# Sheet0-mcu.net
KiCad netlist of a schematic drawn in Altium Designer
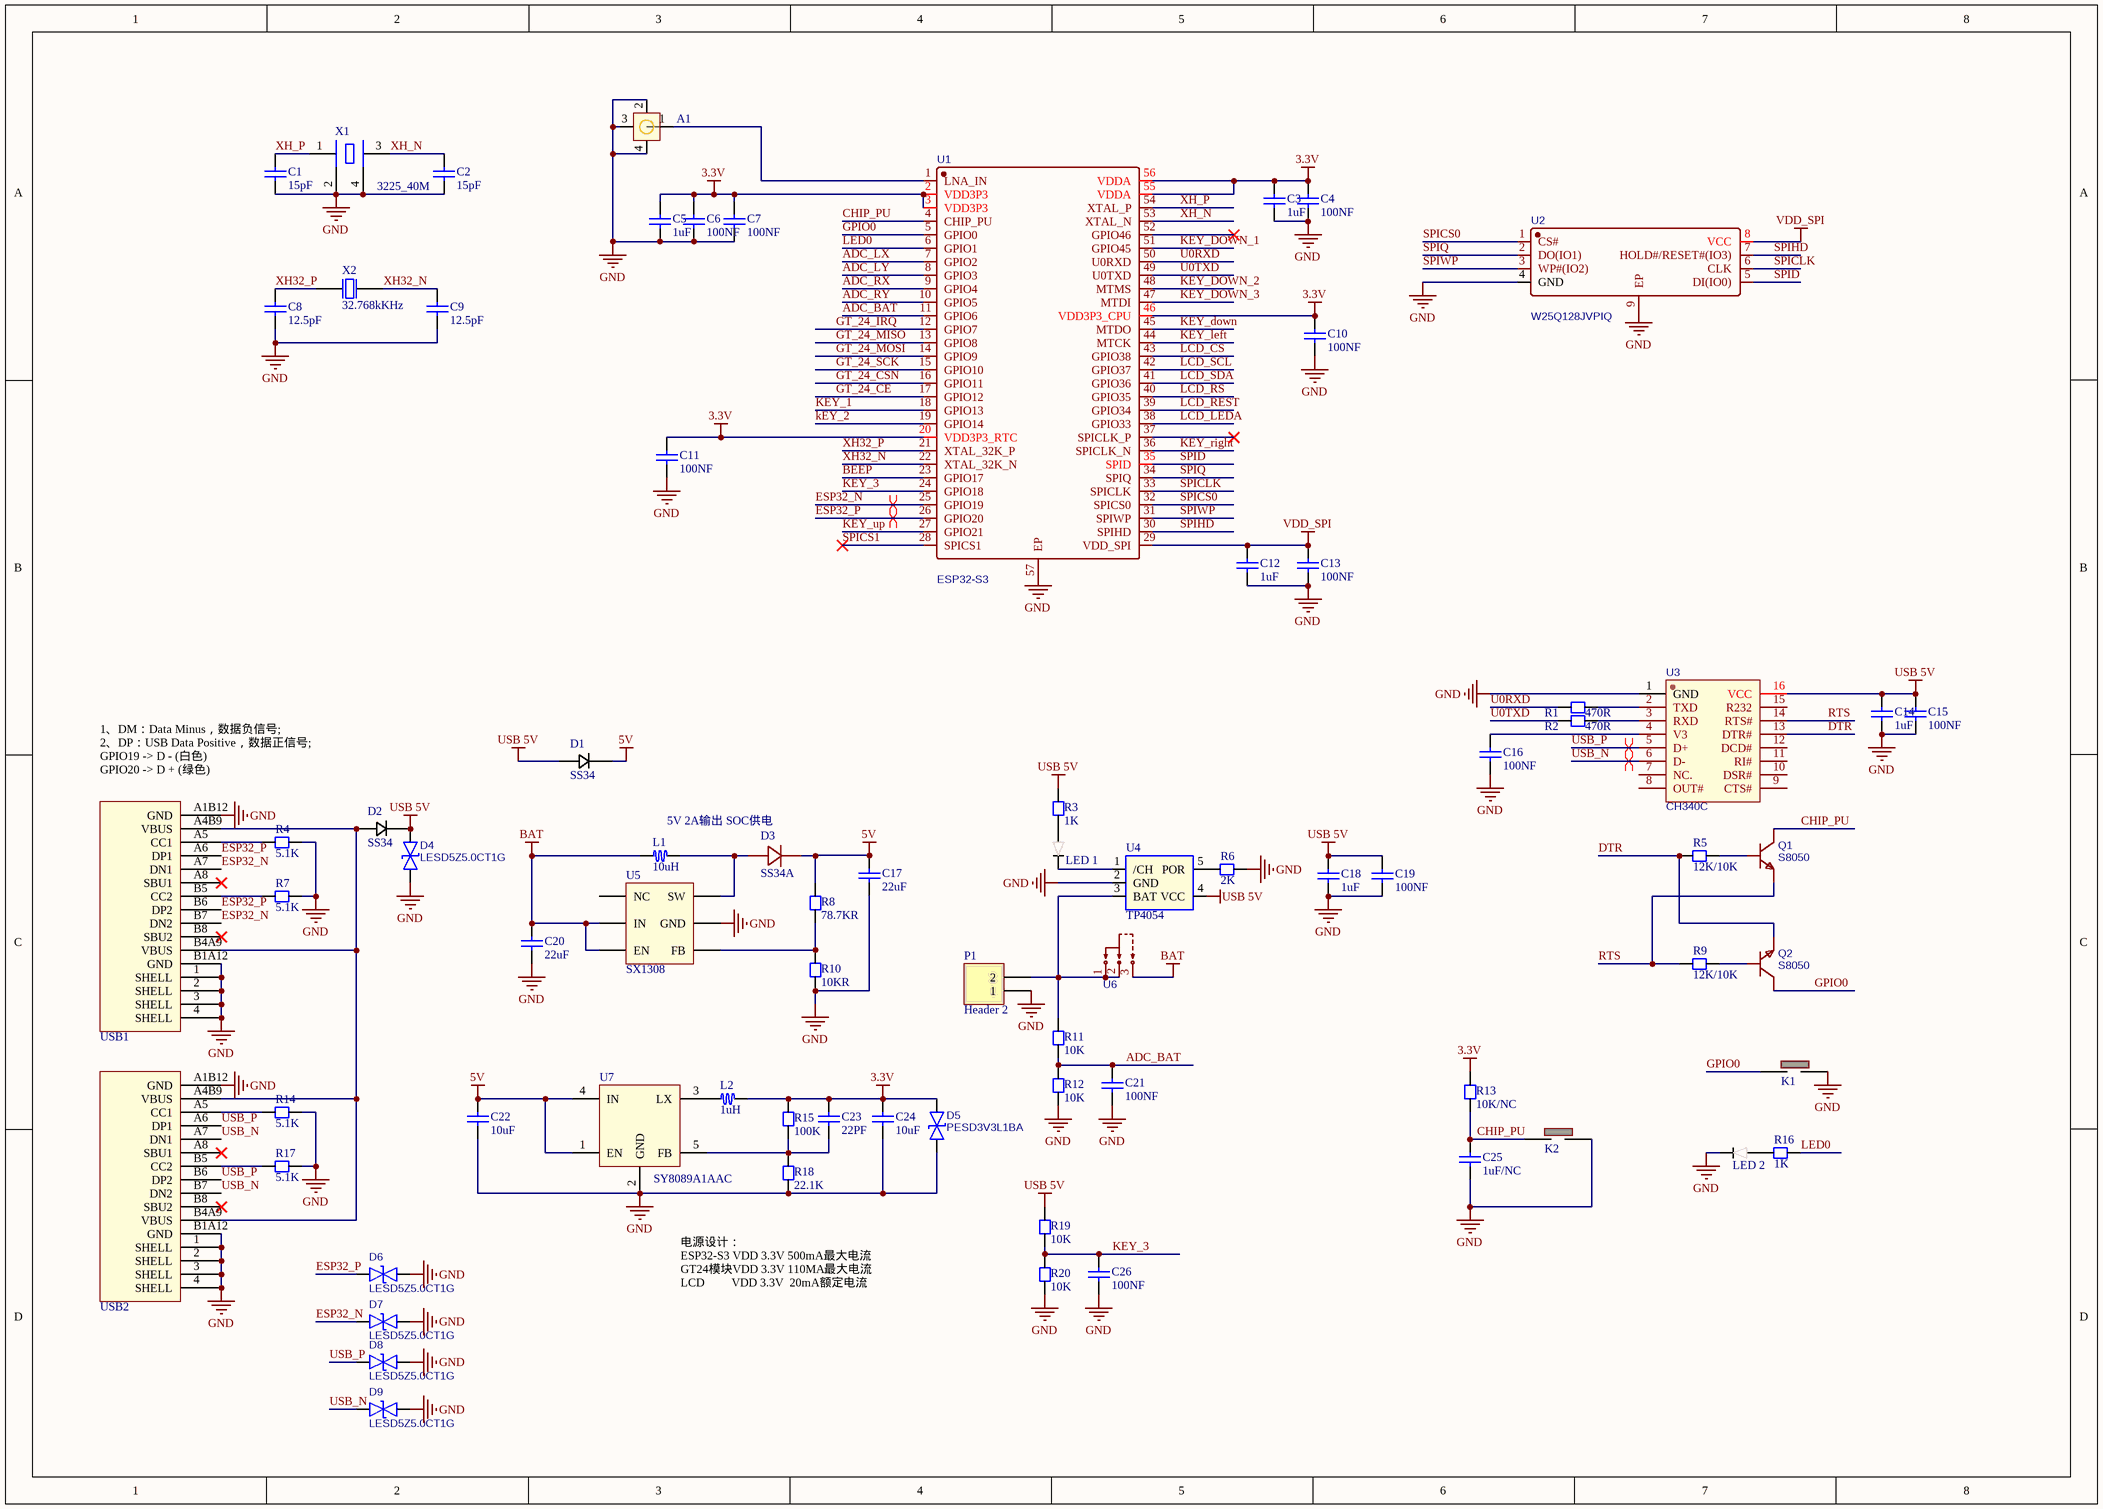
[diagram p0: Sheet0-mcu.SchDoc]

(export (version "E")
  (design (tool "Eeschema 10.0.6"))
  (components
    (comp (ref "A1")
      (value "ANT-IPEX")
      (footprint "ANT-IPEX")
      (description "贴片封装的天线 封装类型为IPEX")
      (libsource (lib "antenna") (part "ANT-IPEX"))
    )
    (comp (ref "C1")
      (value "15pF")
      (footprint "CC1608-0603")
      (description "0603封装的电容")
      (fields (field (name "PUBLISHER") "Altium Limited"))
      (libsource (lib "base") (part "Cap Chip 0603"))
    )
    (comp (ref "C2")
      (value "15pF")
      (footprint "CC1608-0603")
      (description "0603封装的电容")
      (fields (field (name "PUBLISHER") "Altium Limited"))
      (libsource (lib "base") (part "Cap Chip 0603"))
    )
    (comp (ref "C3")
      (value "1uF")
      (footprint "CC1608-0603")
      (description "0603封装的电容")
      (fields (field (name "PUBLISHER") "Altium Limited"))
      (libsource (lib "base") (part "Cap Chip 0603"))
    )
    (comp (ref "C4")
      (value "100NF")
      (footprint "CC1608-0603")
      (description "0603封装的电容")
      (fields (field (name "PUBLISHER") "Altium Limited"))
      (libsource (lib "base") (part "Cap Chip 0603"))
    )
    (comp (ref "C5")
      (value "1uF")
      (footprint "CC1608-0603")
      (description "0603封装的电容")
      (fields (field (name "PUBLISHER") "Altium Limited"))
      (libsource (lib "base") (part "Cap Chip 0603"))
    )
    (comp (ref "C6")
      (value "100NF")
      (footprint "CC1608-0603")
      (description "0603封装的电容")
      (fields (field (name "PUBLISHER") "Altium Limited"))
      (libsource (lib "base") (part "Cap Chip 0603"))
    )
    (comp (ref "C7")
      (value "100NF")
      (footprint "CC1608-0603")
      (description "0603封装的电容")
      (fields (field (name "PUBLISHER") "Altium Limited"))
      (libsource (lib "base") (part "Cap Chip 0603"))
    )
    (comp (ref "C8")
      (value "12.5pF")
      (footprint "CC1608-0603")
      (description "0603封装的电容")
      (fields (field (name "PUBLISHER") "Altium Limited"))
      (libsource (lib "base") (part "Cap Chip 0603"))
    )
    (comp (ref "C9")
      (value "12.5pF")
      (footprint "CC1608-0603")
      (description "0603封装的电容")
      (fields (field (name "PUBLISHER") "Altium Limited"))
      (libsource (lib "base") (part "Cap Chip 0603"))
    )
    (comp (ref "C10")
      (value "100NF")
      (footprint "CC1608-0603")
      (description "0603封装的电容")
      (fields (field (name "PUBLISHER") "Altium Limited"))
      (libsource (lib "base") (part "Cap Chip 0603"))
    )
    (comp (ref "C11")
      (value "100NF")
      (footprint "CC1608-0603")
      (description "0603封装的电容")
      (fields (field (name "PUBLISHER") "Altium Limited"))
      (libsource (lib "base") (part "Cap Chip 0603"))
    )
    (comp (ref "C12")
      (value "1uF")
      (footprint "CC1608-0603")
      (description "0603封装的电容")
      (fields (field (name "PUBLISHER") "Altium Limited"))
      (libsource (lib "base") (part "Cap Chip 0603"))
    )
    (comp (ref "C13")
      (value "100NF")
      (footprint "CC1608-0603")
      (description "0603封装的电容")
      (fields (field (name "PUBLISHER") "Altium Limited"))
      (libsource (lib "base") (part "Cap Chip 0603"))
    )
    (comp (ref "C14")
      (value "1uF")
      (footprint "CC1608-0603")
      (description "0603封装的电容")
      (fields (field (name "PUBLISHER") "Altium Limited"))
      (libsource (lib "base") (part "Cap Chip 0603"))
    )
    (comp (ref "C15")
      (value "100NF")
      (footprint "CC1608-0603")
      (description "0603封装的电容")
      (fields (field (name "PUBLISHER") "Altium Limited"))
      (libsource (lib "base") (part "Cap Chip 0603"))
    )
    (comp (ref "C16")
      (value "100NF")
      (footprint "CC1608-0603")
      (description "0603封装的电容")
      (fields (field (name "PUBLISHER") "Altium Limited"))
      (libsource (lib "base") (part "Cap Chip 0603"))
    )
    (comp (ref "C17")
      (value "22uF")
      (footprint "CC1608-0603")
      (description "贴片电容")
      (libsource (lib "tianxiaohua_Schlib") (part "Chip capacitor"))
    )
    (comp (ref "C18")
      (value "1uF")
      (footprint "CC1608-0603")
      (description "0603封装的电容")
      (fields (field (name "PUBLISHER") "Altium Limited"))
      (libsource (lib "base") (part "Cap Chip 0603"))
    )
    (comp (ref "C19")
      (value "100NF")
      (footprint "CC1608-0603")
      (description "0603封装的电容")
      (fields (field (name "PUBLISHER") "Altium Limited"))
      (libsource (lib "base") (part "Cap Chip 0603"))
    )
    (comp (ref "C20")
      (value "22uF")
      (footprint "CC1608-0603")
      (description "0603封装的电容")
      (fields (field (name "PUBLISHER") "Altium Limited"))
      (libsource (lib "base") (part "Cap Chip 0603"))
    )
    (comp (ref "C21")
      (value "100NF")
      (footprint "CC1608-0603")
      (description "0603封装的电容")
      (fields (field (name "PUBLISHER") "Altium Limited"))
      (libsource (lib "base") (part "Cap Chip 0603"))
    )
    (comp (ref "C22")
      (value "10uF")
      (footprint "CC1608-0603")
      (description "0603封装的电容")
      (fields (field (name "PUBLISHER") "Altium Limited"))
      (libsource (lib "base") (part "Cap Chip 0603"))
    )
    (comp (ref "C23")
      (value "22PF")
      (footprint "CC1608-0603")
      (description "0603封装的电容")
      (fields (field (name "PUBLISHER") "Altium Limited"))
      (libsource (lib "base") (part "Cap Chip 0603"))
    )
    (comp (ref "C24")
      (value "10uF")
      (footprint "CC1608-0603")
      (description "0603封装的电容")
      (fields (field (name "PUBLISHER") "Altium Limited"))
      (libsource (lib "base") (part "Cap Chip 0603"))
    )
    (comp (ref "C25")
      (value "1uF/NC")
      (footprint "CC1608-0603")
      (description "0603封装的电容")
      (fields (field (name "PUBLISHER") "Altium Limited"))
      (libsource (lib "base") (part "Cap Chip 0603"))
    )
    (comp (ref "C26")
      (value "100NF")
      (footprint "CC1608-0603")
      (description "0603封装的电容")
      (fields (field (name "PUBLISHER") "Altium Limited"))
      (libsource (lib "base") (part "Cap Chip 0603"))
    )
    (comp (ref "D1")
      (value "SS34")
      (footprint "DO-214 AA")
      (description "肖特基二极管")
      (libsource (lib "transistor") (part "SS34"))
    )
    (comp (ref "D2")
      (value "SS34")
      (footprint "DO-214 AA")
      (description "肖特基二极管")
      (libsource (lib "transistor") (part "SS34"))
    )
    (comp (ref "D3")
      (value "SS34A")
      (footprint "DO-214 AA SMB")
      (description "大电流肖特基二极管，5A/40V")
      (libsource (lib "tianxiaohua_Schlib") (part "SS34A"))
    )
    (comp (ref "D4")
      (value "LESD5Z5.0CT1G")
      (footprint "SOD-523")
      (description "SOD-523 ESD防静电二极管保护芯片")
      (fields (field (name "MANUFACTURER") "MDD") (field (name "MANUFACTURER PART") "SMAJ6.5CA"))
      (libsource (lib "transistor") (part "LESD5Z5.0CT1G"))
    )
    (comp (ref "D5")
      (value "PESD3V3L1BA")
      (footprint "SOD-323")
      (description "SOD-323 3.3V 双向ESD防静电二极管保护芯片")
      (fields (field (name "MANUFACTURER") "MDD") (field (name "MANUFACTURER PART") "SMAJ6.5CA"))
      (libsource (lib "transistor") (part "PESD3V3L1BA"))
    )
    (comp (ref "D6")
      (value "LESD5Z5.0CT1G")
      (footprint "SOD-523")
      (description "SOD-523 ESD防静电二极管保护芯片")
      (fields (field (name "MANUFACTURER") "MDD") (field (name "MANUFACTURER PART") "SMAJ6.5CA"))
      (libsource (lib "transistor") (part "LESD5Z5.0CT1G"))
    )
    (comp (ref "D7")
      (value "LESD5Z5.0CT1G")
      (footprint "SOD-523")
      (description "SOD-523 ESD防静电二极管保护芯片")
      (fields (field (name "MANUFACTURER") "MDD") (field (name "MANUFACTURER PART") "SMAJ6.5CA"))
      (libsource (lib "transistor") (part "LESD5Z5.0CT1G"))
    )
    (comp (ref "D8")
      (value "LESD5Z5.0CT1G")
      (footprint "SOD-523")
      (description "SOD-523 ESD防静电二极管保护芯片")
      (fields (field (name "MANUFACTURER") "MDD") (field (name "MANUFACTURER PART") "SMAJ6.5CA"))
      (libsource (lib "transistor") (part "LESD5Z5.0CT1G"))
    )
    (comp (ref "D9")
      (value "LESD5Z5.0CT1G")
      (footprint "SOD-523")
      (description "SOD-523 ESD防静电二极管保护芯片")
      (fields (field (name "MANUFACTURER") "MDD") (field (name "MANUFACTURER PART") "SMAJ6.5CA"))
      (libsource (lib "transistor") (part "LESD5Z5.0CT1G"))
    )
    (comp (ref "K1")
      (value "KEY 3*4")
      (footprint "KEY 3*4")
      (description "轻触开关按键")
      (libsource (lib "base") (part "KEY 3*4"))
    )
    (comp (ref "K2")
      (value "KEY 3*4")
      (footprint "KEY 3*4")
      (description "轻触开关按键")
      (libsource (lib "base") (part "KEY 3*4"))
    )
    (comp (ref "L1")
      (value "10uH")
      (footprint "Inductor-6045")
      (description "6045封装 线绕SMD功率电感")
      (libsource (lib "base") (part "Inductor-6045"))
    )
    (comp (ref "L2")
      (value "1uH")
      (footprint "Inductor-4018")
      (description "贴片电感 1206封装")
      (libsource (lib "base") (part "Inductor-4018"))
    )
    (comp (ref "LED 1") (value "LED 0603") (footprint "LED 0603") (libsource (lib "base") (part "LED 0603")))
    (comp (ref "LED 2") (value "LED 0603") (footprint "LED 0603") (libsource (lib "base") (part "LED 0603")))
    (comp (ref "P1")
      (value "Header 2")
      (footprint "HX2.54-2")
      (description "Header, 2-Pin")
      (fields (field (name "PUBLISHER") "Altium Limited"))
      (libsource (lib "Connectors") (part "Header 2"))
    )
    (comp (ref "Q1")
      (value "S8050")
      (footprint "SOT-23")
      (fields (field (name "MANUFACTURER") "SALLTECH(萨瑞)") (field (name "CONTRIBUTOR") "lcsc"))
      (libsource (lib "transistor") (part "S8050"))
    )
    (comp (ref "Q2")
      (value "S8050")
      (footprint "SOT-23")
      (fields (field (name "MANUFACTURER") "SALLTECH(萨瑞)") (field (name "CONTRIBUTOR") "lcsc"))
      (libsource (lib "transistor") (part "S8050"))
    )
    (comp (ref "R1")
      (value "470R")
      (footprint "CR1608-0603")
      (description "0603封装电阻")
      (fields (field (name "PUBLISHER") "Altium Limited"))
      (libsource (lib "base") (part "Resistor Chip 0603"))
    )
    (comp (ref "R2")
      (value "470R")
      (footprint "CR1608-0603")
      (description "0603封装电阻")
      (fields (field (name "PUBLISHER") "Altium Limited"))
      (libsource (lib "base") (part "Resistor Chip 0603"))
    )
    (comp (ref "R3")
      (value "1K")
      (footprint "CR1608-0603")
      (description "0603封装电阻")
      (fields (field (name "PUBLISHER") "Altium Limited"))
      (libsource (lib "") (part "Resistor Chip 0603_1"))
    )
    (comp (ref "R4")
      (value "5.1K")
      (footprint "CR1608-0603")
      (description "0603封装电阻")
      (fields (field (name "PUBLISHER") "Altium Limited"))
      (libsource (lib "base") (part "Resistor Chip 0603"))
    )
    (comp (ref "R5")
      (value "12K/10K")
      (footprint "CR1608-0603")
      (description "0603封装电阻")
      (fields (field (name "PUBLISHER") "Altium Limited"))
      (libsource (lib "") (part "Resistor Chip 0603_3"))
    )
    (comp (ref "R6")
      (value "2K")
      (footprint "CR1608-0603")
      (description "0603封装电阻")
      (fields (field (name "PUBLISHER") "Altium Limited"))
      (libsource (lib "") (part "Resistor Chip 0603_3"))
    )
    (comp (ref "R7")
      (value "5.1K")
      (footprint "CR1608-0603")
      (description "0603封装电阻")
      (fields (field (name "PUBLISHER") "Altium Limited"))
      (libsource (lib "base") (part "Resistor Chip 0603"))
    )
    (comp (ref "R8")
      (value "78.7KR")
      (footprint "CR1608-0603")
      (description "贴片电阻")
      (libsource (lib "tianxiaohua_Schlib") (part "Chip resistor"))
    )
    (comp (ref "R9")
      (value "12K/10K")
      (footprint "CR1608-0603")
      (description "0603封装电阻")
      (fields (field (name "PUBLISHER") "Altium Limited"))
      (libsource (lib "") (part "Resistor Chip 0603_2"))
    )
    (comp (ref "R10")
      (value "10KR")
      (footprint "CR1608-0603")
      (description "贴片电阻")
      (libsource (lib "tianxiaohua_Schlib") (part "Chip resistor"))
    )
    (comp (ref "R11")
      (value "10K")
      (footprint "CR1608-0603")
      (description "0603封装电阻")
      (fields (field (name "PUBLISHER") "Altium Limited"))
      (libsource (lib "") (part "Resistor Chip 0603_2"))
    )
    (comp (ref "R12")
      (value "10K")
      (footprint "CR1608-0603")
      (description "0603封装电阻")
      (fields (field (name "PUBLISHER") "Altium Limited"))
      (libsource (lib "") (part "Resistor Chip 0603_2"))
    )
    (comp (ref "R13")
      (value "10K/NC")
      (footprint "CR1608-0603")
      (description "0603封装电阻")
      (fields (field (name "PUBLISHER") "Altium Limited"))
      (libsource (lib "") (part "Resistor Chip 0603_2"))
    )
    (comp (ref "R14")
      (value "5.1K")
      (footprint "CR1608-0603")
      (description "0603封装电阻")
      (fields (field (name "PUBLISHER") "Altium Limited"))
      (libsource (lib "base") (part "Resistor Chip 0603"))
    )
    (comp (ref "R15")
      (value "100K")
      (footprint "CR1608-0603")
      (description "0603封装电阻")
      (fields (field (name "PUBLISHER") "Altium Limited"))
      (libsource (lib "") (part "Resistor Chip 0603_1"))
    )
    (comp (ref "R16")
      (value "1K")
      (footprint "CR1608-0603")
      (description "0603封装电阻")
      (fields (field (name "PUBLISHER") "Altium Limited"))
      (libsource (lib "base") (part "Resistor Chip 0603"))
    )
    (comp (ref "R17")
      (value "5.1K")
      (footprint "CR1608-0603")
      (description "0603封装电阻")
      (fields (field (name "PUBLISHER") "Altium Limited"))
      (libsource (lib "base") (part "Resistor Chip 0603"))
    )
    (comp (ref "R18")
      (value "22.1K")
      (footprint "CR1608-0603")
      (description "0603封装电阻")
      (fields (field (name "PUBLISHER") "Altium Limited"))
      (libsource (lib "") (part "Resistor Chip 0603_1"))
    )
    (comp (ref "R19")
      (value "10K")
      (footprint "CR1608-0603")
      (description "0603封装电阻")
      (fields (field (name "PUBLISHER") "Altium Limited"))
      (libsource (lib "") (part "Resistor Chip 0603_2"))
    )
    (comp (ref "R20")
      (value "10K")
      (footprint "CR1608-0603")
      (description "0603封装电阻")
      (fields (field (name "PUBLISHER") "Altium Limited"))
      (libsource (lib "") (part "Resistor Chip 0603_2"))
    )
    (comp (ref "U1")
      (value "ESP32-S3")
      (footprint "QFN-56")
      (fields (field (name "MANUFACTURER") "ESPRESSIF(乐鑫)") (field (name "CONTRIBUTOR") "LCSC"))
      (libsource (lib "singlechip") (part "ESP32-S3"))
    )
    (comp (ref "U2")
      (value "W25Q128JVPIQ")
      (footprint "WSON-8")
      (fields (field (name "MANUFACTURER") "WINBOND(华邦)") (field (name "CONTRIBUTOR") "LCSC"))
      (libsource (lib "PB-Chip") (part "W25Q128JVPIQ"))
    )
    (comp (ref "U3")
      (value "CH340C")
      (footprint "SOP-16")
      (fields (field (name "MANUFACTURER") "WCH(南京沁恒)"))
      (libsource (lib "PB-Chip") (part "CH340C"))
    )
    (comp (ref "U4")
      (value "TP4054")
      (footprint "SOT23-5")
      (description "迷你充电IC SOT-23-5")
      (libsource (lib "power-chip") (part "TP4054"))
    )
    (comp (ref "U5")
      (value "SX1308")
      (footprint "SOT23-6")
      (description "SOT23-6 升压芯片")
      (libsource (lib "power-chip") (part "SX1308"))
    )
    (comp (ref "U6")
      (value "HX SS12D10G4")
      (footprint "SW-TH_3P-SS12D06")
      (fields (field (name "BOM_SUPPLIER PART") "C5149841") (field (name "CONTRIBUTOR") "lcsc"))
      (libsource (lib "base") (part "SW-TH_3P-SS12D06"))
    )
    (comp (ref "U7")
      (value "SY8089A1AAC")
      (footprint "SOT23-5")
      (libsource (lib "power-chip") (part "SY8089A1AAC"))
    )
    (comp (ref "USB1")
      (value "Tpye-c 16P")
      (footprint "TYPE-C 16P")
      (description "16P 封装的TYPE -c接口 4固定插脚 双向")
      (libsource (lib "Connectors") (part "Tpye-c 16P"))
    )
    (comp (ref "USB2")
      (value "Tpye-c 16P")
      (footprint "TYPE-C 16P")
      (description "16P 封装的TYPE -c接口 4固定插脚 双向")
      (libsource (lib "Connectors") (part "Tpye-c 16P"))
    )
    (comp (ref "X1")
      (value "3225_40M")
      (footprint "XTAL-3225")
      (description "3225封装的晶振")
      (libsource (lib "base") (part "XTAL 3225"))
    )
    (comp (ref "X2")
      (value "32.768kKHz")
      (footprint "XTAL-3215")
      (description "3215封装的时钟晶振")
      (libsource (lib "base") (part "XTAL 3215 32.768kKHz"))
    )
  )
  (nets
    (net (code "1") (name "/ADC_BAT") (class "Default")
      (node (ref "C21") (pin "2") (pinfunction "2_2") (pintype "passive"))
      (node (ref "R11") (pin "1") (pinfunction "1_1") (pintype "passive"))
      (node (ref "R12") (pin "2") (pinfunction "2_2") (pintype "passive"))
      (node (ref "U1") (pin "11") (pinfunction "GPIO6_11") (pintype "passive"))
    )
    (net (code "2") (name "/ADC_LX") (class "Default")
      (node (ref "U1") (pin "7") (pinfunction "GPIO2_7") (pintype "passive"))
    )
    (net (code "3") (name "/ADC_LY") (class "Default")
      (node (ref "U1") (pin "8") (pinfunction "GPIO3_8") (pintype "passive"))
    )
    (net (code "4") (name "/ADC_RX") (class "Default")
      (node (ref "U1") (pin "9") (pinfunction "GPIO4_9") (pintype "passive"))
    )
    (net (code "5") (name "/ADC_RY") (class "Default")
      (node (ref "U1") (pin "10") (pinfunction "GPIO5_10") (pintype "passive"))
    )
    (net (code "6") (name "/BEEP") (class "Default")
      (node (ref "U1") (pin "23") (pinfunction "GPIO17_23") (pintype "passive"))
    )
    (net (code "7") (name "/CHIP_PU") (class "Default")
      (node (ref "C25") (pin "2") (pinfunction "2_2") (pintype "passive"))
      (node (ref "K2") (pin "1") (pinfunction "1_1") (pintype "passive"))
      (node (ref "Q1") (pin "3") (pinfunction "C_3") (pintype "passive"))
      (node (ref "R13") (pin "1") (pinfunction "1_1") (pintype "passive"))
      (node (ref "U1") (pin "4") (pinfunction "CHIP_PU_4") (pintype "passive"))
    )
    (net (code "8") (name "/DTR") (class "Default")
      (node (ref "Q2") (pin "2") (pinfunction "E_2") (pintype "passive"))
      (node (ref "R5") (pin "1") (pinfunction "1_1") (pintype "passive"))
      (node (ref "U3") (pin "13") (pinfunction "DTR#_13") (pintype "passive"))
    )
    (net (code "9") (name "/ESP32_N") (class "Default")
      (node (ref "D7") (pin "1") (pinfunction "1_1") (pintype "passive"))
      (node (ref "U1") (pin "25") (pinfunction "GPIO19_25") (pintype "passive"))
      (node (ref "USB1") (pin "A7") (pinfunction "DN1_A7") (pintype "power_in"))
      (node (ref "USB1") (pin "B7") (pinfunction "DN2_B7") (pintype "power_in"))
    )
    (net (code "10") (name "/ESP32_P") (class "Default")
      (node (ref "D6") (pin "1") (pinfunction "1_1") (pintype "passive"))
      (node (ref "U1") (pin "26") (pinfunction "GPIO20_26") (pintype "passive"))
      (node (ref "USB1") (pin "A6") (pinfunction "DP1_A6") (pintype "power_in"))
      (node (ref "USB1") (pin "B6") (pinfunction "DP2_B6") (pintype "power_in"))
    )
    (net (code "11") (name "/GPIO0") (class "Default")
      (node (ref "K1") (pin "1") (pinfunction "1_1") (pintype "passive"))
      (node (ref "Q2") (pin "3") (pinfunction "C_3") (pintype "passive"))
      (node (ref "U1") (pin "5") (pinfunction "GPIO0_5") (pintype "passive"))
    )
    (net (code "12") (name "/GT_24_CE") (class "Default")
      (node (ref "U1") (pin "17") (pinfunction "GPIO12_17") (pintype "passive"))
    )
    (net (code "13") (name "/GT_24_CSN") (class "Default")
      (node (ref "U1") (pin "16") (pinfunction "GPIO11_16") (pintype "passive"))
    )
    (net (code "14") (name "/GT_24_IRQ") (class "Default")
      (node (ref "U1") (pin "12") (pinfunction "GPIO7_12") (pintype "passive"))
    )
    (net (code "15") (name "/GT_24_MISO") (class "Default")
      (node (ref "U1") (pin "13") (pinfunction "GPIO8_13") (pintype "passive"))
    )
    (net (code "16") (name "/GT_24_MOSI") (class "Default")
      (node (ref "U1") (pin "14") (pinfunction "GPIO9_14") (pintype "passive"))
    )
    (net (code "17") (name "/GT_24_SCK") (class "Default")
      (node (ref "U1") (pin "15") (pinfunction "GPIO10_15") (pintype "passive"))
    )
    (net (code "18") (name "/KEY_1") (class "Default")
      (node (ref "U1") (pin "18") (pinfunction "GPIO13_18") (pintype "passive"))
    )
    (net (code "19") (name "/KEY_3") (class "Default")
      (node (ref "C26") (pin "2") (pinfunction "2_2") (pintype "passive"))
      (node (ref "R19") (pin "1") (pinfunction "1_1") (pintype "passive"))
      (node (ref "R20") (pin "2") (pinfunction "2_2") (pintype "passive"))
      (node (ref "U1") (pin "24") (pinfunction "GPIO18_24") (pintype "passive"))
    )
    (net (code "20") (name "/KEY_DOWN_1") (class "Default")
      (node (ref "U1") (pin "51") (pinfunction "GPIO45_51") (pintype "passive"))
    )
    (net (code "21") (name "/KEY_DOWN_2") (class "Default")
      (node (ref "U1") (pin "48") (pinfunction "MTMS_48") (pintype "passive"))
    )
    (net (code "22") (name "/KEY_DOWN_3") (class "Default")
      (node (ref "U1") (pin "47") (pinfunction "MTDI_47") (pintype "passive"))
    )
    (net (code "23") (name "/KEY_down") (class "Default")
      (node (ref "U1") (pin "45") (pinfunction "MTDO_45") (pintype "passive"))
    )
    (net (code "24") (name "/KEY_left") (class "Default")
      (node (ref "U1") (pin "44") (pinfunction "MTCK_44") (pintype "passive"))
    )
    (net (code "25") (name "/KEY_right") (class "Default")
      (node (ref "U1") (pin "36") (pinfunction "SPICLK_N_36") (pintype "passive"))
    )
    (net (code "26") (name "/KEY_up") (class "Default")
      (node (ref "U1") (pin "27") (pinfunction "GPIO21_27") (pintype "passive"))
    )
    (net (code "27") (name "/LCD_CS") (class "Default")
      (node (ref "U1") (pin "43") (pinfunction "GPIO38_43") (pintype "passive"))
    )
    (net (code "28") (name "/LCD_LEDA") (class "Default")
      (node (ref "U1") (pin "38") (pinfunction "GPIO33_38") (pintype "passive"))
    )
    (net (code "29") (name "/LCD_REST") (class "Default")
      (node (ref "U1") (pin "39") (pinfunction "GPIO34_39") (pintype "passive"))
    )
    (net (code "30") (name "/LCD_RS") (class "Default")
      (node (ref "U1") (pin "40") (pinfunction "GPIO35_40") (pintype "passive"))
    )
    (net (code "31") (name "/LCD_SCL") (class "Default")
      (node (ref "U1") (pin "42") (pinfunction "GPIO37_42") (pintype "passive"))
    )
    (net (code "32") (name "/LCD_SDA") (class "Default")
      (node (ref "U1") (pin "41") (pinfunction "GPIO36_41") (pintype "passive"))
    )
    (net (code "33") (name "/LED0") (class "Default")
      (node (ref "R16") (pin "1") (pinfunction "1_1") (pintype "passive"))
      (node (ref "U1") (pin "6") (pinfunction "GPIO1_6") (pintype "passive"))
    )
    (net (code "34") (name "/RTS") (class "Default")
      (node (ref "Q1") (pin "2") (pinfunction "E_2") (pintype "passive"))
      (node (ref "R9") (pin "1") (pinfunction "1_1") (pintype "passive"))
      (node (ref "U3") (pin "14") (pinfunction "RTS#_14") (pintype "passive"))
    )
    (net (code "35") (name "/SPICLK") (class "Default")
      (node (ref "U1") (pin "33") (pinfunction "SPICLK_33") (pintype "passive"))
      (node (ref "U2") (pin "6") (pinfunction "CLK_6") (pintype "passive"))
    )
    (net (code "36") (name "/SPICS0") (class "Default")
      (node (ref "U1") (pin "32") (pinfunction "SPICS0_32") (pintype "passive"))
      (node (ref "U2") (pin "1") (pinfunction "CS#_1") (pintype "passive"))
    )
    (net (code "37") (name "/SPICS1") (class "Default")
      (node (ref "U1") (pin "28") (pinfunction "SPICS1_28") (pintype "passive+no_connect"))
    )
    (net (code "38") (name "/SPID") (class "Default")
      (node (ref "U1") (pin "35") (pinfunction "SPID_35") (pintype "passive"))
      (node (ref "U2") (pin "5") (pinfunction "DI(IO0)_5") (pintype "passive"))
    )
    (net (code "39") (name "/SPIHD") (class "Default")
      (node (ref "U1") (pin "30") (pinfunction "SPIHD_30") (pintype "passive"))
      (node (ref "U2") (pin "7") (pinfunction "HOLD#/RESET#(IO3)_7") (pintype "passive"))
    )
    (net (code "40") (name "/SPIQ") (class "Default")
      (node (ref "U1") (pin "34") (pinfunction "SPIQ_34") (pintype "passive"))
      (node (ref "U2") (pin "2") (pinfunction "DO(IO1)_2") (pintype "passive"))
    )
    (net (code "41") (name "/SPIWP") (class "Default")
      (node (ref "U1") (pin "31") (pinfunction "SPIWP_31") (pintype "passive"))
      (node (ref "U2") (pin "3") (pinfunction "WP#(IO2)_3") (pintype "passive"))
    )
    (net (code "42") (name "/U0RXD") (class "Default")
      (node (ref "R1") (pin "2") (pinfunction "2_2") (pintype "passive"))
      (node (ref "U1") (pin "50") (pinfunction "U0RXD_50") (pintype "passive"))
    )
    (net (code "43") (name "/U0TXD") (class "Default")
      (node (ref "R2") (pin "2") (pinfunction "2_2") (pintype "passive"))
      (node (ref "U1") (pin "49") (pinfunction "U0TXD_49") (pintype "passive"))
    )
    (net (code "44") (name "/USB_N") (class "Default")
      (node (ref "D9") (pin "1") (pinfunction "1_1") (pintype "passive"))
      (node (ref "U3") (pin "6") (pinfunction "D-_6") (pintype "passive"))
      (node (ref "USB2") (pin "A7") (pinfunction "DN1_A7") (pintype "power_in"))
      (node (ref "USB2") (pin "B7") (pinfunction "DN2_B7") (pintype "power_in"))
    )
    (net (code "45") (name "/USB_P") (class "Default")
      (node (ref "D8") (pin "1") (pinfunction "1_1") (pintype "passive"))
      (node (ref "U3") (pin "5") (pinfunction "D+_5") (pintype "passive"))
      (node (ref "USB2") (pin "A6") (pinfunction "DP1_A6") (pintype "power_in"))
      (node (ref "USB2") (pin "B6") (pinfunction "DP2_B6") (pintype "power_in"))
    )
    (net (code "46") (name "/XH32_N") (class "Default")
      (node (ref "C9") (pin "2") (pinfunction "2_2") (pintype "passive"))
      (node (ref "U1") (pin "22") (pinfunction "XTAL_32K_N_22") (pintype "passive"))
      (node (ref "X2") (pin "2") (pinfunction "OSC2_2") (pintype "passive"))
    )
    (net (code "47") (name "/XH32_P") (class "Default")
      (node (ref "C8") (pin "2") (pinfunction "2_2") (pintype "passive"))
      (node (ref "U1") (pin "21") (pinfunction "XTAL_32K_P_21") (pintype "passive"))
      (node (ref "X2") (pin "1") (pinfunction "OSC1_1") (pintype "passive"))
    )
    (net (code "48") (name "/XH_N") (class "Default")
      (node (ref "C2") (pin "2") (pinfunction "2_2") (pintype "passive"))
      (node (ref "U1") (pin "53") (pinfunction "XTAL_N_53") (pintype "passive"))
      (node (ref "X1") (pin "3") (pinfunction "OSC2_3") (pintype "passive"))
    )
    (net (code "49") (name "/XH_P") (class "Default")
      (node (ref "C1") (pin "2") (pinfunction "2_2") (pintype "passive"))
      (node (ref "U1") (pin "54") (pinfunction "XTAL_P_54") (pintype "passive"))
      (node (ref "X1") (pin "1") (pinfunction "OSC1_1") (pintype "passive"))
    )
    (net (code "50") (name "/kEY_2") (class "Default")
      (node (ref "U1") (pin "19") (pinfunction "GPIO14_19") (pintype "passive"))
    )
    (net (code "51") (name "3.3V") (class "Default")
      (node (ref "C10") (pin "2") (pinfunction "2_2") (pintype "passive"))
      (node (ref "C11") (pin "2") (pinfunction "2_2") (pintype "passive"))
      (node (ref "C23") (pin "2") (pinfunction "2_2") (pintype "passive"))
      (node (ref "C24") (pin "2") (pinfunction "2_2") (pintype "passive"))
      (node (ref "C3") (pin "2") (pinfunction "2_2") (pintype "passive"))
      (node (ref "C4") (pin "2") (pinfunction "2_2") (pintype "passive"))
      (node (ref "C5") (pin "2") (pinfunction "2_2") (pintype "passive"))
      (node (ref "C6") (pin "2") (pinfunction "2_2") (pintype "passive"))
      (node (ref "C7") (pin "2") (pinfunction "2_2") (pintype "passive"))
      (node (ref "D5") (pin "1") (pinfunction "1_1") (pintype "passive"))
      (node (ref "L2") (pin "2") (pinfunction "2_2") (pintype "passive"))
      (node (ref "R13") (pin "2") (pinfunction "2_2") (pintype "passive"))
      (node (ref "R15") (pin "1") (pinfunction "1_1") (pintype "passive"))
      (node (ref "U1") (pin "2") (pinfunction "VDD3P3_2") (pintype "passive"))
      (node (ref "U1") (pin "20") (pinfunction "VDD3P3_RTC_20") (pintype "passive"))
      (node (ref "U1") (pin "3") (pinfunction "VDD3P3_3") (pintype "passive"))
      (node (ref "U1") (pin "46") (pinfunction "VDD3P3_CPU_46") (pintype "passive"))
      (node (ref "U1") (pin "55") (pinfunction "VDDA_55") (pintype "passive"))
      (node (ref "U1") (pin "56") (pinfunction "VDDA_56") (pintype "passive"))
    )
    (net (code "52") (name "5V") (class "Default")
      (node (ref "C17") (pin "1") (pinfunction "1_1") (pintype "passive"))
      (node (ref "C22") (pin "2") (pinfunction "2_2") (pintype "passive"))
      (node (ref "D1") (pin "1") (pinfunction "K_1") (pintype "passive"))
      (node (ref "D3") (pin "1") (pinfunction "C_1") (pintype "passive"))
      (node (ref "R8") (pin "2") (pinfunction "2_2") (pintype "passive"))
      (node (ref "U7") (pin "1") (pinfunction "EN_1") (pintype "passive"))
      (node (ref "U7") (pin "4") (pinfunction "IN_4") (pintype "passive"))
    )
    (net (code "53") (name "BAT") (class "Default")
      (node (ref "C20") (pin "2") (pinfunction "2_2") (pintype "passive"))
      (node (ref "L1") (pin "1") (pinfunction "1_1") (pintype "passive"))
      (node (ref "U5") (pin "4") (pinfunction "EN_4") (pintype "passive"))
      (node (ref "U5") (pin "5") (pinfunction "IN_5") (pintype "passive"))
      (node (ref "U6") (pin "3") (pinfunction "3_3") (pintype "passive"))
    )
    (net (code "54") (name "GND") (class "Default")
      (node (ref "A1") (pin "2") (pinfunction "2_2") (pintype "passive"))
      (node (ref "A1") (pin "3") (pinfunction "3_3") (pintype "passive"))
      (node (ref "A1") (pin "4") (pinfunction "4_4") (pintype "passive"))
      (node (ref "C1") (pin "1") (pinfunction "1_1") (pintype "passive"))
      (node (ref "C10") (pin "1") (pinfunction "1_1") (pintype "passive"))
      (node (ref "C11") (pin "1") (pinfunction "1_1") (pintype "passive"))
      (node (ref "C12") (pin "1") (pinfunction "1_1") (pintype "passive"))
      (node (ref "C13") (pin "1") (pinfunction "1_1") (pintype "passive"))
      (node (ref "C14") (pin "1") (pinfunction "1_1") (pintype "passive"))
      (node (ref "C15") (pin "1") (pinfunction "1_1") (pintype "passive"))
      (node (ref "C16") (pin "1") (pinfunction "1_1") (pintype "passive"))
      (node (ref "C17") (pin "2") (pinfunction "2_2") (pintype "passive"))
      (node (ref "C18") (pin "1") (pinfunction "1_1") (pintype "passive"))
      (node (ref "C19") (pin "1") (pinfunction "1_1") (pintype "passive"))
      (node (ref "C2") (pin "1") (pinfunction "1_1") (pintype "passive"))
      (node (ref "C20") (pin "1") (pinfunction "1_1") (pintype "passive"))
      (node (ref "C21") (pin "1") (pinfunction "1_1") (pintype "passive"))
      (node (ref "C22") (pin "1") (pinfunction "1_1") (pintype "passive"))
      (node (ref "C24") (pin "1") (pinfunction "1_1") (pintype "passive"))
      (node (ref "C25") (pin "1") (pinfunction "1_1") (pintype "passive"))
      (node (ref "C26") (pin "1") (pinfunction "1_1") (pintype "passive"))
      (node (ref "C3") (pin "1") (pinfunction "1_1") (pintype "passive"))
      (node (ref "C4") (pin "1") (pinfunction "1_1") (pintype "passive"))
      (node (ref "C5") (pin "1") (pinfunction "1_1") (pintype "passive"))
      (node (ref "C6") (pin "1") (pinfunction "1_1") (pintype "passive"))
      (node (ref "C7") (pin "1") (pinfunction "1_1") (pintype "passive"))
      (node (ref "C8") (pin "1") (pinfunction "1_1") (pintype "passive"))
      (node (ref "C9") (pin "1") (pinfunction "1_1") (pintype "passive"))
      (node (ref "D4") (pin "2") (pinfunction "2_2") (pintype "passive"))
      (node (ref "D5") (pin "2") (pinfunction "2_2") (pintype "passive"))
      (node (ref "D6") (pin "2") (pinfunction "2_2") (pintype "passive"))
      (node (ref "D7") (pin "2") (pinfunction "2_2") (pintype "passive"))
      (node (ref "D8") (pin "2") (pinfunction "2_2") (pintype "passive"))
      (node (ref "D9") (pin "2") (pinfunction "2_2") (pintype "passive"))
      (node (ref "K1") (pin "2") (pinfunction "2_2") (pintype "passive"))
      (node (ref "K2") (pin "2") (pinfunction "2_2") (pintype "passive"))
      (node (ref "LED 2") (pin "2") (pinfunction "2_2") (pintype "passive"))
      (node (ref "P1") (pin "1") (pinfunction "1_1") (pintype "passive"))
      (node (ref "R10") (pin "1") (pinfunction "1_1") (pintype "passive"))
      (node (ref "R12") (pin "1") (pinfunction "1_1") (pintype "passive"))
      (node (ref "R14") (pin "1") (pinfunction "1_1") (pintype "passive"))
      (node (ref "R17") (pin "1") (pinfunction "1_1") (pintype "passive"))
      (node (ref "R18") (pin "2") (pinfunction "2_2") (pintype "passive"))
      (node (ref "R20") (pin "1") (pinfunction "1_1") (pintype "passive"))
      (node (ref "R4") (pin "1") (pinfunction "1_1") (pintype "passive"))
      (node (ref "R6") (pin "2") (pinfunction "2_2") (pintype "passive"))
      (node (ref "R7") (pin "1") (pinfunction "1_1") (pintype "passive"))
      (node (ref "U1") (pin "57") (pinfunction "EP_57") (pintype "passive"))
      (node (ref "U2") (pin "4") (pinfunction "GND_4") (pintype "passive"))
      (node (ref "U2") (pin "9") (pinfunction "EP_9") (pintype "passive"))
      (node (ref "U3") (pin "1") (pinfunction "GND_1") (pintype "passive"))
      (node (ref "U4") (pin "2") (pinfunction "GND_2") (pintype "passive"))
      (node (ref "U5") (pin "2") (pinfunction "GND_2") (pintype "passive"))
      (node (ref "U7") (pin "2") (pinfunction "GND_2") (pintype "passive"))
      (node (ref "USB1") (pin "1") (pinfunction "SHELL_1") (pintype "power_in"))
      (node (ref "USB1") (pin "2") (pinfunction "SHELL_2") (pintype "power_in"))
      (node (ref "USB1") (pin "3") (pinfunction "SHELL_3") (pintype "power_in"))
      (node (ref "USB1") (pin "4") (pinfunction "SHELL_4") (pintype "power_in"))
      (node (ref "USB1") (pin "A1B12") (pinfunction "GND_A1B12") (pintype "power_in"))
      (node (ref "USB1") (pin "B1A12") (pinfunction "GND_B1A12") (pintype "power_in"))
      (node (ref "USB2") (pin "1") (pinfunction "SHELL_1") (pintype "power_in"))
      (node (ref "USB2") (pin "2") (pinfunction "SHELL_2") (pintype "power_in"))
      (node (ref "USB2") (pin "3") (pinfunction "SHELL_3") (pintype "power_in"))
      (node (ref "USB2") (pin "4") (pinfunction "SHELL_4") (pintype "power_in"))
      (node (ref "USB2") (pin "A1B12") (pinfunction "GND_A1B12") (pintype "power_in"))
      (node (ref "USB2") (pin "B1A12") (pinfunction "GND_B1A12") (pintype "power_in"))
      (node (ref "X1") (pin "2") (pinfunction "GND_2") (pintype "passive"))
      (node (ref "X1") (pin "4") (pinfunction "GND_4") (pintype "passive"))
    )
    (net (code "55") (name "Net-(D2-A)") (class "Default")
      (node (ref "D2") (pin "2") (pinfunction "A_2") (pintype "passive"))
      (node (ref "USB1") (pin "A4B9") (pinfunction "VBUS_A4B9") (pintype "power_in"))
      (node (ref "USB1") (pin "B4A9") (pinfunction "VBUS_B4A9") (pintype "power_in"))
      (node (ref "USB2") (pin "A4B9") (pinfunction "VBUS_A4B9") (pintype "power_in"))
      (node (ref "USB2") (pin "B4A9") (pinfunction "VBUS_B4A9") (pintype "power_in"))
    )
    (net (code "56") (name "Net-(D3-A)") (class "Default")
      (node (ref "D3") (pin "2") (pinfunction "A_2") (pintype "passive"))
      (node (ref "L1") (pin "2") (pinfunction "2_2") (pintype "passive"))
      (node (ref "U5") (pin "1") (pinfunction "SW_1") (pintype "passive"))
    )
    (net (code "57") (name "Net-(LED 1-Pad1)") (class "Default")
      (node (ref "LED 1") (pin "1") (pinfunction "1_1") (pintype "passive"))
      (node (ref "R3") (pin "2") (pinfunction "2_2") (pintype "passive"))
    )
    (net (code "58") (name "Net-(LED 2-Pad1)") (class "Default")
      (node (ref "LED 2") (pin "1") (pinfunction "1_1") (pintype "passive"))
      (node (ref "R16") (pin "2") (pinfunction "2_2") (pintype "passive"))
    )
    (net (code "59") (name "Net-(Q1-B)") (class "Default")
      (node (ref "Q1") (pin "1") (pinfunction "B_1") (pintype "passive"))
      (node (ref "R5") (pin "2") (pinfunction "2_2") (pintype "passive"))
    )
    (net (code "60") (name "Net-(Q2-B)") (class "Default")
      (node (ref "Q2") (pin "1") (pinfunction "B_1") (pintype "passive"))
      (node (ref "R9") (pin "2") (pinfunction "2_2") (pintype "passive"))
    )
    (net (code "61") (name "Net-(U1-LNA_IN)") (class "Default")
      (node (ref "A1") (pin "1") (pinfunction "1_1") (pintype "passive"))
      (node (ref "U1") (pin "1") (pinfunction "LNA_IN_1") (pintype "passive"))
    )
    (net (code "62") (name "Net-(U3-RXD)") (class "Default")
      (node (ref "R2") (pin "1") (pinfunction "1_1") (pintype "passive"))
      (node (ref "U3") (pin "3") (pinfunction "RXD_3") (pintype "passive"))
    )
    (net (code "63") (name "Net-(U3-TXD)") (class "Default")
      (node (ref "R1") (pin "1") (pinfunction "1_1") (pintype "passive"))
      (node (ref "U3") (pin "2") (pinfunction "TXD_2") (pintype "passive"))
    )
    (net (code "64") (name "Net-(U3-V3)") (class "Default")
      (node (ref "C16") (pin "2") (pinfunction "2_2") (pintype "passive"))
      (node (ref "U3") (pin "4") (pinfunction "V3_4") (pintype "passive"))
    )
    (net (code "65") (name "Net-(U4-BAT)") (class "Default")
      (node (ref "P1") (pin "2") (pinfunction "2_2") (pintype "passive"))
      (node (ref "R11") (pin "2") (pinfunction "2_2") (pintype "passive"))
      (node (ref "U4") (pin "3") (pinfunction "BAT_3") (pintype "passive"))
      (node (ref "U6") (pin "1") (pinfunction "1_1") (pintype "passive"))
      (node (ref "U6") (pin "2") (pinfunction "2_2") (pintype "passive"))
    )
    (net (code "66") (name "Net-(U4-POR)") (class "Default")
      (node (ref "R6") (pin "1") (pinfunction "1_1") (pintype "passive"))
      (node (ref "U4") (pin "5") (pinfunction "POR_5") (pintype "passive"))
    )
    (net (code "67") (name "Net-(U4-{slash}CH)") (class "Default")
      (node (ref "LED 1") (pin "2") (pinfunction "2_2") (pintype "passive"))
      (node (ref "U4") (pin "1") (pinfunction "/CH_1") (pintype "passive"))
    )
    (net (code "68") (name "Net-(U5-FB)") (class "Default")
      (node (ref "R10") (pin "2") (pinfunction "2_2") (pintype "passive"))
      (node (ref "R8") (pin "1") (pinfunction "1_1") (pintype "passive"))
      (node (ref "U5") (pin "3") (pinfunction "FB_3") (pintype "passive"))
    )
    (net (code "69") (name "Net-(U7-FB)") (class "Default")
      (node (ref "C23") (pin "1") (pinfunction "1_1") (pintype "passive"))
      (node (ref "R15") (pin "2") (pinfunction "2_2") (pintype "passive"))
      (node (ref "R18") (pin "1") (pinfunction "1_1") (pintype "passive"))
      (node (ref "U7") (pin "5") (pinfunction "FB_5") (pintype "passive"))
    )
    (net (code "70") (name "Net-(U7-LX)") (class "Default")
      (node (ref "L2") (pin "1") (pinfunction "1_1") (pintype "passive"))
      (node (ref "U7") (pin "3") (pinfunction "LX_3") (pintype "passive"))
    )
    (net (code "71") (name "Net-(USB1-CC1)") (class "Default")
      (node (ref "R4") (pin "2") (pinfunction "2_2") (pintype "passive"))
      (node (ref "USB1") (pin "A5") (pinfunction "CC1_A5") (pintype "power_in"))
    )
    (net (code "72") (name "Net-(USB1-CC2)") (class "Default")
      (node (ref "R7") (pin "2") (pinfunction "2_2") (pintype "passive"))
      (node (ref "USB1") (pin "B5") (pinfunction "CC2_B5") (pintype "power_in"))
    )
    (net (code "73") (name "Net-(USB2-CC1)") (class "Default")
      (node (ref "R14") (pin "2") (pinfunction "2_2") (pintype "passive"))
      (node (ref "USB2") (pin "A5") (pinfunction "CC1_A5") (pintype "power_in"))
    )
    (net (code "74") (name "Net-(USB2-CC2)") (class "Default")
      (node (ref "R17") (pin "2") (pinfunction "2_2") (pintype "passive"))
      (node (ref "USB2") (pin "B5") (pinfunction "CC2_B5") (pintype "power_in"))
    )
    (net (code "75") (name "USB 5V") (class "Default")
      (node (ref "C14") (pin "2") (pinfunction "2_2") (pintype "passive"))
      (node (ref "C15") (pin "2") (pinfunction "2_2") (pintype "passive"))
      (node (ref "C18") (pin "2") (pinfunction "2_2") (pintype "passive"))
      (node (ref "C19") (pin "2") (pinfunction "2_2") (pintype "passive"))
      (node (ref "D1") (pin "2") (pinfunction "A_2") (pintype "passive"))
      (node (ref "D2") (pin "1") (pinfunction "K_1") (pintype "passive"))
      (node (ref "D4") (pin "1") (pinfunction "1_1") (pintype "passive"))
      (node (ref "R19") (pin "2") (pinfunction "2_2") (pintype "passive"))
      (node (ref "R3") (pin "1") (pinfunction "1_1") (pintype "passive"))
      (node (ref "U3") (pin "16") (pinfunction "VCC_16") (pintype "passive"))
      (node (ref "U4") (pin "4") (pinfunction "VCC_4") (pintype "passive"))
    )
    (net (code "76") (name "VDD_SPI") (class "Default")
      (node (ref "C12") (pin "2") (pinfunction "2_2") (pintype "passive"))
      (node (ref "C13") (pin "2") (pinfunction "2_2") (pintype "passive"))
      (node (ref "U1") (pin "29") (pinfunction "VDD_SPI_29") (pintype "passive"))
      (node (ref "U2") (pin "8") (pinfunction "VCC_8") (pintype "passive"))
    )
    (net (code "77") (name "unconnected-(U1-GPIO46-Pad52)") (class "Default")
      (node (ref "U1") (pin "52") (pinfunction "GPIO46_52") (pintype "passive+no_connect"))
    )
    (net (code "78") (name "unconnected-(U1-SPICLK_P-Pad37)") (class "Default")
      (node (ref "U1") (pin "37") (pinfunction "SPICLK_P_37") (pintype "passive+no_connect"))
    )
    (net (code "79") (name "unconnected-(U3-CTS#-Pad9)") (class "Default")
      (node (ref "U3") (pin "9") (pinfunction "CTS#_9") (pintype "passive"))
    )
    (net (code "80") (name "unconnected-(U3-DCD#-Pad12)") (class "Default")
      (node (ref "U3") (pin "12") (pinfunction "DCD#_12") (pintype "passive"))
    )
    (net (code "81") (name "unconnected-(U3-DSR#-Pad10)") (class "Default")
      (node (ref "U3") (pin "10") (pinfunction "DSR#_10") (pintype "passive"))
    )
    (net (code "82") (name "unconnected-(U3-NC.-Pad7)") (class "Default")
      (node (ref "U3") (pin "7") (pinfunction "NC._7") (pintype "passive"))
    )
    (net (code "83") (name "unconnected-(U3-OUT#-Pad8)") (class "Default")
      (node (ref "U3") (pin "8") (pinfunction "OUT#_8") (pintype "passive"))
    )
    (net (code "84") (name "unconnected-(U3-R232-Pad15)") (class "Default")
      (node (ref "U3") (pin "15") (pinfunction "R232_15") (pintype "passive"))
    )
    (net (code "85") (name "unconnected-(U3-RI#-Pad11)") (class "Default")
      (node (ref "U3") (pin "11") (pinfunction "RI#_11") (pintype "passive"))
    )
    (net (code "86") (name "unconnected-(U5-NC-Pad6)") (class "Default")
      (node (ref "U5") (pin "6") (pinfunction "NC_6") (pintype "passive"))
    )
    (net (code "87") (name "unconnected-(USB1-SBU1-PadA8)") (class "Default")
      (node (ref "USB1") (pin "A8") (pinfunction "SBU1_A8") (pintype "power_in+no_connect"))
    )
    (net (code "88") (name "unconnected-(USB1-SBU2-PadB8)") (class "Default")
      (node (ref "USB1") (pin "B8") (pinfunction "SBU2_B8") (pintype "power_in+no_connect"))
    )
    (net (code "89") (name "unconnected-(USB2-SBU1-PadA8)") (class "Default")
      (node (ref "USB2") (pin "A8") (pinfunction "SBU1_A8") (pintype "power_in+no_connect"))
    )
    (net (code "90") (name "unconnected-(USB2-SBU2-PadB8)") (class "Default")
      (node (ref "USB2") (pin "B8") (pinfunction "SBU2_B8") (pintype "power_in+no_connect"))
    )
  )
)
